# EEM_connector_Magneto.net
KiCad netlist of a schematic drawn in Altium Designer
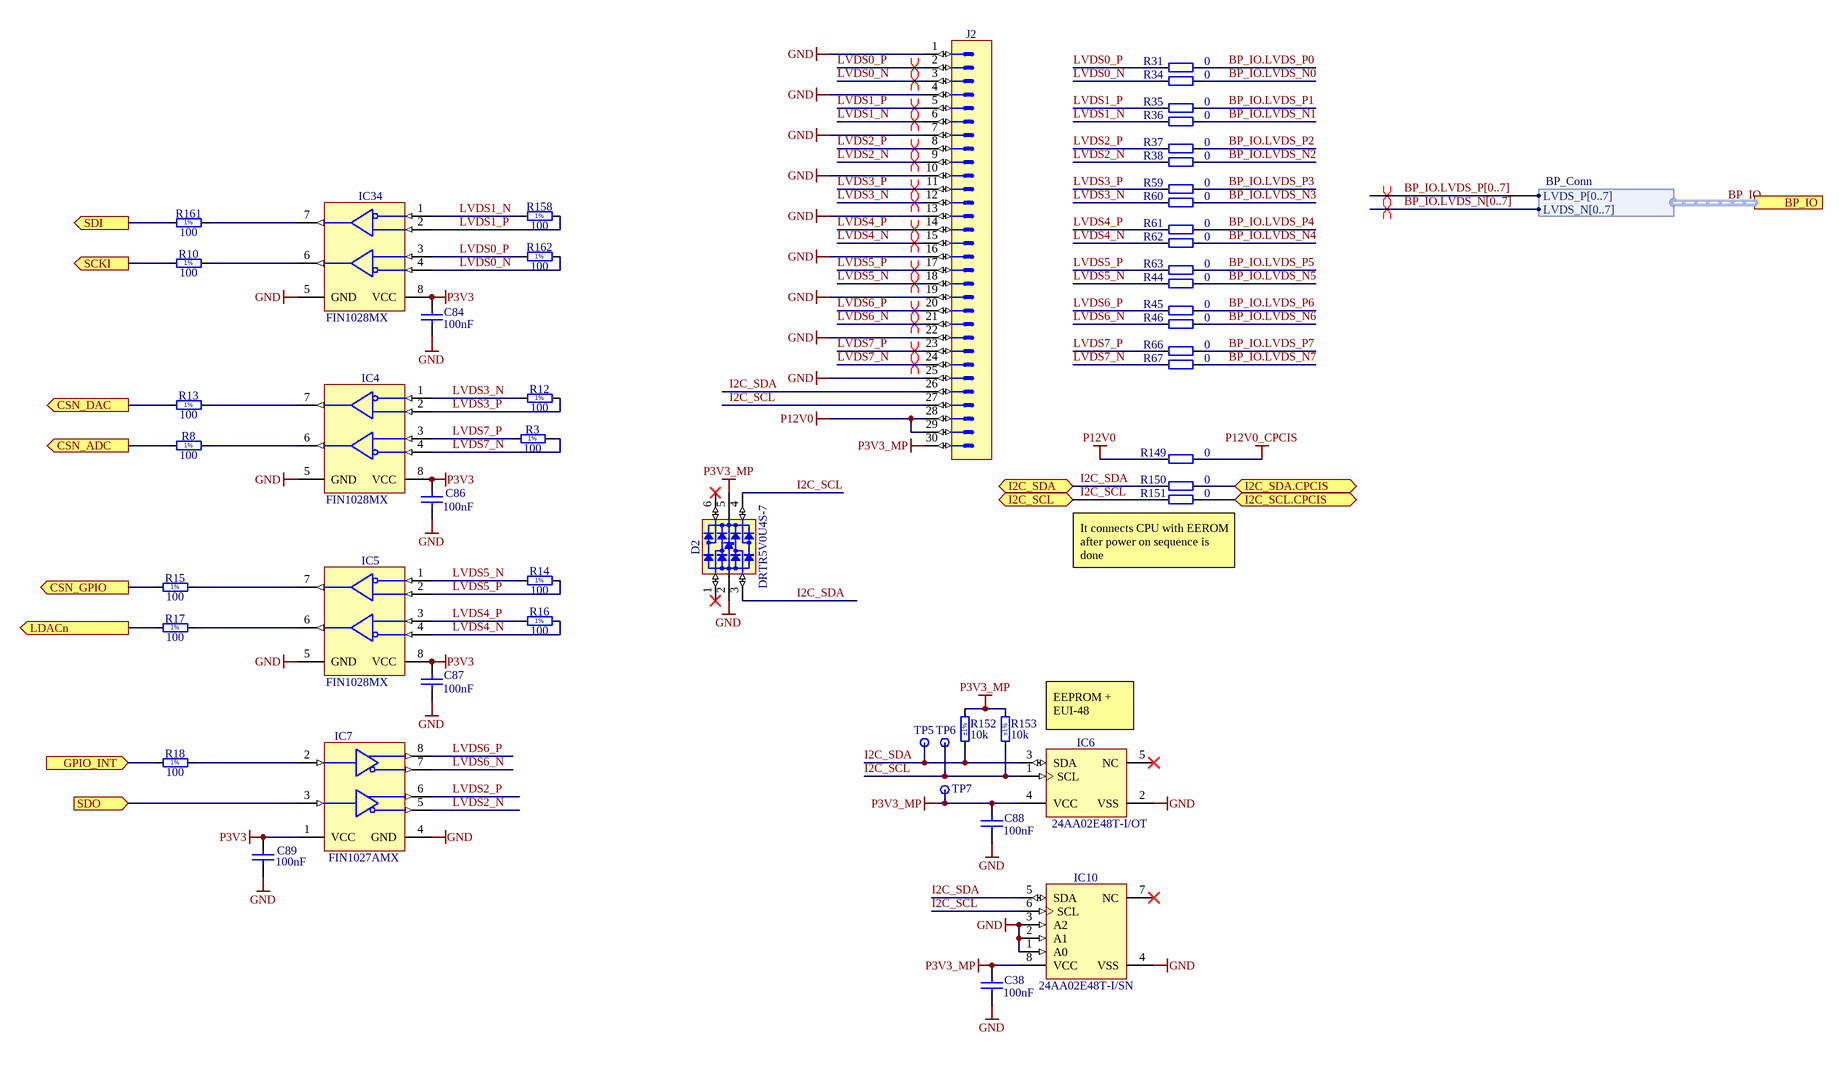
[diagram p0: EEM_connector_Magneto.SchDoc]

(export (version "E")
  (design (tool "Eeschema 10.0.6"))
  (components
    (comp (ref "C38")
      (value "100nF")
      (footprint "CAPC1005X55N")
      (description "Non-polarised capacitor")
      (fields
        (field (name "PART NUMBER") "CC0402_100NF_16V_10%_X5R")
        (field (name "VOLTAGE") "16V")
        (field (name "AUTHOR") "CERN DEM JLC")
      )
      (libsource (lib "Capacitors") (part "Capacitor - non polarized"))
    )
    (comp (ref "C84")
      (value "100nF")
      (footprint "CAPC1005X55N")
      (description "Non-polarised capacitor")
      (fields
        (field (name "PART NUMBER") "CC0402_100NF_16V_10%_X5R")
        (field (name "VOLTAGE") "16V")
        (field (name "AUTHOR") "CERN DEM JLC")
      )
      (libsource (lib "Capacitors") (part "Capacitor - non polarized"))
    )
    (comp (ref "C86")
      (value "100nF")
      (footprint "CAPC1005X55N")
      (description "Non-polarised capacitor")
      (fields
        (field (name "PART NUMBER") "CC0402_100NF_16V_10%_X5R")
        (field (name "VOLTAGE") "16V")
        (field (name "AUTHOR") "CERN DEM JLC")
      )
      (libsource (lib "Capacitors") (part "Capacitor - non polarized"))
    )
    (comp (ref "C87")
      (value "100nF")
      (footprint "CAPC1005X55N")
      (description "Non-polarised capacitor")
      (fields
        (field (name "PART NUMBER") "CC0402_100NF_16V_10%_X5R")
        (field (name "VOLTAGE") "16V")
        (field (name "AUTHOR") "CERN DEM JLC")
      )
      (libsource (lib "Capacitors") (part "Capacitor - non polarized"))
    )
    (comp (ref "C88")
      (value "100nF")
      (footprint "CAPC1005X55N")
      (description "Non-polarised capacitor")
      (fields
        (field (name "PART NUMBER") "CC0402_100NF_16V_10%_X5R")
        (field (name "VOLTAGE") "16V")
        (field (name "AUTHOR") "CERN DEM JLC")
      )
      (libsource (lib "Capacitors") (part "Capacitor - non polarized"))
    )
    (comp (ref "C89")
      (value "100nF")
      (footprint "CAPC1005X55N")
      (description "Non-polarised capacitor")
      (fields
        (field (name "PART NUMBER") "CC0402_100NF_16V_10%_X5R")
        (field (name "VOLTAGE") "16V")
        (field (name "AUTHOR") "CERN DEM JLC")
      )
      (libsource (lib "Capacitors") (part "Capacitor - non polarized"))
    )
    (comp (ref "D2")
      (value "DRTR5V0U4S-7")
      (footprint "SOT65P210X110-6N")
      (description "Integrated Quad Ultra-Low Capacitance ESD Protection")
      (fields (field (name "AUTHOR") "GK"))
      (libsource (lib "Diodes") (part "D_TVS_DRTR5V0U4S-7"))
    )
    (comp (ref "IC4")
      (value "FIN1028MX")
      (footprint "SOIC127P600X175-8N")
      (description "3.3V LVDS 2-Bit High-Speed Differential Reciever")
      (fields (field (name "AUTHOR") "GK"))
      (libsource (lib "LIBRARY_SCH") (part "IFC_FIN1028"))
    )
    (comp (ref "IC5")
      (value "FIN1028MX")
      (footprint "SOIC127P600X175-8N")
      (description "3.3V LVDS 2-Bit High-Speed Differential Reciever")
      (fields (field (name "AUTHOR") "GK"))
      (libsource (lib "LIBRARY_SCH") (part "IFC_FIN1028"))
    )
    (comp (ref "IC6")
      (value "24AA02E48T-I/OT")
      (footprint "SOT95P280X145-5N")
      (description "1.7V-5.5V, 2K I2C Serial EEPROM With EUI-48 Node Identity")
      (fields (field (name "MANUFACTURER") "MICROCHIP TECHNOLOGY") (field (name "AUTHOR") "CERN DEM MR"))
      (libsource (lib "ICs And Semiconductors") (part "24AA02E48T-I/OT"))
    )
    (comp (ref "IC7")
      (value "FIN1027AMX")
      (footprint "SOIC127P600X175-8N")
      (description "3.3V LVDS, 2-Bit, High-Speed, Differential Driver")
      (fields (field (name "AUTHOR") "GK"))
      (libsource (lib "LIBRARY_SCH") (part "IFC_FIN1027A"))
    )
    (comp (ref "IC10")
      (value "24AA02E48T-I/SN")
      (footprint "SOIC127P600X175-8N")
      (description "1.7V-5.5V, 2K I2C™ Serial EEPROMs with EUI-48™ Node Identity")
      (fields (field (name "AUTHOR") "CERN DEM MR"))
      (libsource (lib "ICs And Semiconductors") (part "24AA025E48-I/SN"))
    )
    (comp (ref "IC34")
      (value "FIN1028MX")
      (footprint "SOIC127P600X175-8N")
      (description "3.3V LVDS 2-Bit High-Speed Differential Reciever")
      (fields (field (name "AUTHOR") "GK"))
      (libsource (lib "LIBRARY_SCH") (part "IFC_FIN1028"))
    )
    (comp (ref "J2")
      (value "IDC")
      (footprint "3M_N2530-6002RB")
      (description "Connector 30 Male")
      (fields
        (field (name "PART NUMBER") "3M_N2530-6002RB")
        (field (name "MANUFACTURER") "3M")
        (field (name "AUTHOR") "CERN DEM JLC")
      )
      (libsource (lib "Connectors") (part "Connector 30 Male"))
    )
    (comp (ref "R3")
      (value "100")
      (footprint "RESC1005X40N")
      (description "Resistor - 1%")
      (fields
        (field (name "PART NUMBER") "R0402_100R_1%_0.0625W_100PPM")
        (field (name "POWER") "0.0625W")
        (field (name "AUTHOR") "CERN DEM JLC")
      )
      (libsource (lib "Resistors") (part "Resistor - 1%"))
    )
    (comp (ref "R8")
      (value "100")
      (footprint "RESC1005X40N")
      (description "Resistor - 1%")
      (fields
        (field (name "PART NUMBER") "R0402_100R_1%_0.0625W_100PPM")
        (field (name "POWER") "0.0625W")
        (field (name "AUTHOR") "CERN DEM JLC")
      )
      (libsource (lib "Resistors") (part "Resistor - 1%"))
    )
    (comp (ref "R10")
      (value "100")
      (footprint "RESC1005X40N")
      (description "Resistor - 1%")
      (fields
        (field (name "PART NUMBER") "R0402_100R_1%_0.0625W_100PPM")
        (field (name "POWER") "0.0625W")
        (field (name "AUTHOR") "CERN DEM JLC")
      )
      (libsource (lib "Resistors") (part "Resistor - 1%"))
    )
    (comp (ref "R12")
      (value "100")
      (footprint "RESC1005X40N")
      (description "Resistor - 1%")
      (fields
        (field (name "PART NUMBER") "R0402_100R_1%_0.0625W_100PPM")
        (field (name "POWER") "0.0625W")
        (field (name "AUTHOR") "CERN DEM JLC")
      )
      (libsource (lib "Resistors") (part "Resistor - 1%"))
    )
    (comp (ref "R13")
      (value "100")
      (footprint "RESC1005X40N")
      (description "Resistor - 1%")
      (fields
        (field (name "PART NUMBER") "R0402_100R_1%_0.0625W_100PPM")
        (field (name "POWER") "0.0625W")
        (field (name "AUTHOR") "CERN DEM JLC")
      )
      (libsource (lib "Resistors") (part "Resistor - 1%"))
    )
    (comp (ref "R14")
      (value "100")
      (footprint "RESC1005X40N")
      (description "Resistor - 1%")
      (fields
        (field (name "PART NUMBER") "R0402_100R_1%_0.0625W_100PPM")
        (field (name "POWER") "0.0625W")
        (field (name "AUTHOR") "CERN DEM JLC")
      )
      (libsource (lib "Resistors") (part "Resistor - 1%"))
    )
    (comp (ref "R15")
      (value "100")
      (footprint "RESC1005X40N")
      (description "Resistor - 1%")
      (fields
        (field (name "PART NUMBER") "R0402_100R_1%_0.0625W_100PPM")
        (field (name "POWER") "0.0625W")
        (field (name "AUTHOR") "CERN DEM JLC")
      )
      (libsource (lib "Resistors") (part "Resistor - 1%"))
    )
    (comp (ref "R16")
      (value "100")
      (footprint "RESC1005X40N")
      (description "Resistor - 1%")
      (fields
        (field (name "PART NUMBER") "R0402_100R_1%_0.0625W_100PPM")
        (field (name "POWER") "0.0625W")
        (field (name "AUTHOR") "CERN DEM JLC")
      )
      (libsource (lib "Resistors") (part "Resistor - 1%"))
    )
    (comp (ref "R17")
      (value "100")
      (footprint "RESC1005X40N")
      (description "Resistor - 1%")
      (fields
        (field (name "PART NUMBER") "R0402_100R_1%_0.0625W_100PPM")
        (field (name "POWER") "0.0625W")
        (field (name "AUTHOR") "CERN DEM JLC")
      )
      (libsource (lib "Resistors") (part "Resistor - 1%"))
    )
    (comp (ref "R18")
      (value "100")
      (footprint "RESC1005X40N")
      (description "Resistor - 1%")
      (fields
        (field (name "PART NUMBER") "R0402_100R_1%_0.0625W_100PPM")
        (field (name "POWER") "0.0625W")
        (field (name "AUTHOR") "CERN DEM JLC")
      )
      (libsource (lib "Resistors") (part "Resistor - 1%"))
    )
    (comp (ref "R31")
      (value "0")
      (footprint "RESC1005X40N")
      (description "Resistor")
      (fields
        (field (name "PART NUMBER") "R0402_0R_JUMPER")
        (field (name "MANUFACTURER") "GENERIC")
        (field (name "AUTHOR") "CERN DEM JLC")
      )
      (libsource (lib "Resistors") (part "Resistor"))
    )
    (comp (ref "R34")
      (value "0")
      (footprint "RESC1005X40N")
      (description "Resistor")
      (fields
        (field (name "PART NUMBER") "R0402_0R_JUMPER")
        (field (name "MANUFACTURER") "GENERIC")
        (field (name "AUTHOR") "CERN DEM JLC")
      )
      (libsource (lib "Resistors") (part "Resistor"))
    )
    (comp (ref "R35")
      (value "0")
      (footprint "RESC1005X40N")
      (description "Resistor")
      (fields
        (field (name "PART NUMBER") "R0402_0R_JUMPER")
        (field (name "MANUFACTURER") "GENERIC")
        (field (name "AUTHOR") "CERN DEM JLC")
      )
      (libsource (lib "Resistors") (part "Resistor"))
    )
    (comp (ref "R36")
      (value "0")
      (footprint "RESC1005X40N")
      (description "Resistor")
      (fields
        (field (name "PART NUMBER") "R0402_0R_JUMPER")
        (field (name "MANUFACTURER") "GENERIC")
        (field (name "AUTHOR") "CERN DEM JLC")
      )
      (libsource (lib "Resistors") (part "Resistor"))
    )
    (comp (ref "R37")
      (value "0")
      (footprint "RESC1005X40N")
      (description "Resistor")
      (fields
        (field (name "PART NUMBER") "R0402_0R_JUMPER")
        (field (name "MANUFACTURER") "GENERIC")
        (field (name "AUTHOR") "CERN DEM JLC")
      )
      (libsource (lib "Resistors") (part "Resistor"))
    )
    (comp (ref "R38")
      (value "0")
      (footprint "RESC1005X40N")
      (description "Resistor")
      (fields
        (field (name "PART NUMBER") "R0402_0R_JUMPER")
        (field (name "MANUFACTURER") "GENERIC")
        (field (name "AUTHOR") "CERN DEM JLC")
      )
      (libsource (lib "Resistors") (part "Resistor"))
    )
    (comp (ref "R44")
      (value "0")
      (footprint "RESC1005X40N")
      (description "Resistor")
      (fields
        (field (name "PART NUMBER") "R0402_0R_JUMPER")
        (field (name "MANUFACTURER") "GENERIC")
        (field (name "AUTHOR") "CERN DEM JLC")
      )
      (libsource (lib "Resistors") (part "Resistor"))
    )
    (comp (ref "R45")
      (value "0")
      (footprint "RESC1005X40N")
      (description "Resistor")
      (fields
        (field (name "PART NUMBER") "R0402_0R_JUMPER")
        (field (name "MANUFACTURER") "GENERIC")
        (field (name "AUTHOR") "CERN DEM JLC")
      )
      (libsource (lib "Resistors") (part "Resistor"))
    )
    (comp (ref "R46")
      (value "0")
      (footprint "RESC1005X40N")
      (description "Resistor")
      (fields
        (field (name "PART NUMBER") "R0402_0R_JUMPER")
        (field (name "MANUFACTURER") "GENERIC")
        (field (name "AUTHOR") "CERN DEM JLC")
      )
      (libsource (lib "Resistors") (part "Resistor"))
    )
    (comp (ref "R59")
      (value "0")
      (footprint "RESC1005X40N")
      (description "Resistor")
      (fields
        (field (name "PART NUMBER") "R0402_0R_JUMPER")
        (field (name "MANUFACTURER") "GENERIC")
        (field (name "AUTHOR") "CERN DEM JLC")
      )
      (libsource (lib "Resistors") (part "Resistor"))
    )
    (comp (ref "R60")
      (value "0")
      (footprint "RESC1005X40N")
      (description "Resistor")
      (fields
        (field (name "PART NUMBER") "R0402_0R_JUMPER")
        (field (name "MANUFACTURER") "GENERIC")
        (field (name "AUTHOR") "CERN DEM JLC")
      )
      (libsource (lib "Resistors") (part "Resistor"))
    )
    (comp (ref "R61")
      (value "0")
      (footprint "RESC1005X40N")
      (description "Resistor")
      (fields
        (field (name "PART NUMBER") "R0402_0R_JUMPER")
        (field (name "MANUFACTURER") "GENERIC")
        (field (name "AUTHOR") "CERN DEM JLC")
      )
      (libsource (lib "Resistors") (part "Resistor"))
    )
    (comp (ref "R62")
      (value "0")
      (footprint "RESC1005X40N")
      (description "Resistor")
      (fields
        (field (name "PART NUMBER") "R0402_0R_JUMPER")
        (field (name "MANUFACTURER") "GENERIC")
        (field (name "AUTHOR") "CERN DEM JLC")
      )
      (libsource (lib "Resistors") (part "Resistor"))
    )
    (comp (ref "R63")
      (value "0")
      (footprint "RESC1005X40N")
      (description "Resistor")
      (fields
        (field (name "PART NUMBER") "R0402_0R_JUMPER")
        (field (name "MANUFACTURER") "GENERIC")
        (field (name "AUTHOR") "CERN DEM JLC")
      )
      (libsource (lib "Resistors") (part "Resistor"))
    )
    (comp (ref "R66")
      (value "0")
      (footprint "RESC1005X40N")
      (description "Resistor")
      (fields
        (field (name "PART NUMBER") "R0402_0R_JUMPER")
        (field (name "MANUFACTURER") "GENERIC")
        (field (name "AUTHOR") "CERN DEM JLC")
      )
      (libsource (lib "Resistors") (part "Resistor"))
    )
    (comp (ref "R67")
      (value "0")
      (footprint "RESC1005X40N")
      (description "Resistor")
      (fields
        (field (name "PART NUMBER") "R0402_0R_JUMPER")
        (field (name "MANUFACTURER") "GENERIC")
        (field (name "AUTHOR") "CERN DEM JLC")
      )
      (libsource (lib "Resistors") (part "Resistor"))
    )
    (comp (ref "R149")
      (value "0")
      (footprint "RESC2012X60N")
      (description "Resistor")
      (fields
        (field (name "PART NUMBER") "R0805_0R_JUMPER")
        (field (name "MANUFACTURER") "GENERIC")
        (field (name "AUTHOR") "CERN DEM JLC")
      )
      (libsource (lib "Resistors") (part "Resistor"))
    )
    (comp (ref "R150")
      (value "0")
      (footprint "RESC1005X40N")
      (description "Resistor")
      (fields
        (field (name "PART NUMBER") "R0402_0R_JUMPER")
        (field (name "MANUFACTURER") "GENERIC")
        (field (name "AUTHOR") "CERN DEM JLC")
      )
      (libsource (lib "Resistors") (part "Resistor"))
    )
    (comp (ref "R151")
      (value "0")
      (footprint "RESC1005X40N")
      (description "Resistor")
      (fields
        (field (name "PART NUMBER") "R0402_0R_JUMPER")
        (field (name "MANUFACTURER") "GENERIC")
        (field (name "AUTHOR") "CERN DEM JLC")
      )
      (libsource (lib "Resistors") (part "Resistor"))
    )
    (comp (ref "R152")
      (value "10k")
      (footprint "RESC1005X40N")
      (description "Resistor - 1%")
      (fields
        (field (name "TOLERANCE") "±1%")
        (field (name "PART NUMBER") "R0402_10K_1%_0.0625W_100PPM")
        (field (name "POWER") "0.0625W")
        (field (name "AUTHOR") "CERN DEM JLC")
      )
      (libsource (lib "Resistors") (part "Resistor - 1%"))
    )
    (comp (ref "R153")
      (value "10k")
      (footprint "RESC1005X40N")
      (description "Resistor - 1%")
      (fields
        (field (name "TOLERANCE") "±1%")
        (field (name "PART NUMBER") "R0402_10K_1%_0.0625W_100PPM")
        (field (name "POWER") "0.0625W")
        (field (name "AUTHOR") "CERN DEM JLC")
      )
      (libsource (lib "Resistors") (part "Resistor - 1%"))
    )
    (comp (ref "R158")
      (value "100")
      (footprint "RESC1005X40N")
      (description "Resistor - 1%")
      (fields
        (field (name "PART NUMBER") "R0402_100R_1%_0.0625W_100PPM")
        (field (name "POWER") "0.0625W")
        (field (name "AUTHOR") "CERN DEM JLC")
      )
      (libsource (lib "Resistors") (part "Resistor - 1%"))
    )
    (comp (ref "R161")
      (value "100")
      (footprint "RESC1005X40N")
      (description "Resistor - 1%")
      (fields
        (field (name "PART NUMBER") "R0402_100R_1%_0.0625W_100PPM")
        (field (name "POWER") "0.0625W")
        (field (name "AUTHOR") "CERN DEM JLC")
      )
      (libsource (lib "Resistors") (part "Resistor - 1%"))
    )
    (comp (ref "R162")
      (value "100")
      (footprint "RESC1005X40N")
      (description "Resistor - 1%")
      (fields
        (field (name "PART NUMBER") "R0402_100R_1%_0.0625W_100PPM")
        (field (name "POWER") "0.0625W")
        (field (name "AUTHOR") "CERN DEM JLC")
      )
      (libsource (lib "Resistors") (part "Resistor - 1%"))
    )
    (comp (ref "TP5")
      (value "Test Point")
      (footprint "TPS127")
      (fields (field (name "PART NUMBER") "SMD_PAD_1.27X1.27MM") (field (name "AUTHOR") "CERN DEM JLC"))
      (libsource (lib "Eletro-mechanical") (part "Test Point"))
    )
    (comp (ref "TP6")
      (value "Test Point")
      (footprint "TPS127")
      (fields (field (name "PART NUMBER") "SMD_PAD_1.27X1.27MM") (field (name "AUTHOR") "CERN DEM JLC"))
      (libsource (lib "Eletro-mechanical") (part "Test Point"))
    )
    (comp (ref "TP7")
      (value "Test Point")
      (footprint "TPS127")
      (fields (field (name "PART NUMBER") "SMD_PAD_1.27X1.27MM") (field (name "AUTHOR") "CERN DEM JLC"))
      (libsource (lib "Eletro-mechanical") (part "Test Point"))
    )
  )
  (nets
    (net (code "2") (name "/BP_IO.LVDS_N0") (class "Default")
      (node (ref "R34") (pin "2") (pinfunction "2_2") (pintype "passive"))
    )
    (net (code "3") (name "/BP_IO.LVDS_N1") (class "Default")
      (node (ref "R36") (pin "2") (pinfunction "2_2") (pintype "passive"))
    )
    (net (code "4") (name "/BP_IO.LVDS_N2") (class "Default")
      (node (ref "R38") (pin "2") (pinfunction "2_2") (pintype "passive"))
    )
    (net (code "5") (name "/BP_IO.LVDS_N3") (class "Default")
      (node (ref "R60") (pin "2") (pinfunction "2_2") (pintype "passive"))
    )
    (net (code "6") (name "/BP_IO.LVDS_N4") (class "Default")
      (node (ref "R62") (pin "2") (pinfunction "2_2") (pintype "passive"))
    )
    (net (code "7") (name "/BP_IO.LVDS_N5") (class "Default")
      (node (ref "R44") (pin "2") (pinfunction "2_2") (pintype "passive"))
    )
    (net (code "8") (name "/BP_IO.LVDS_N6") (class "Default")
      (node (ref "R46") (pin "2") (pinfunction "2_2") (pintype "passive"))
    )
    (net (code "9") (name "/BP_IO.LVDS_N7") (class "Default")
      (node (ref "R67") (pin "2") (pinfunction "2_2") (pintype "passive"))
    )
    (net (code "11") (name "/BP_IO.LVDS_P0") (class "Default")
      (node (ref "R31") (pin "2") (pinfunction "2_2") (pintype "passive"))
    )
    (net (code "12") (name "/BP_IO.LVDS_P1") (class "Default")
      (node (ref "R35") (pin "2") (pinfunction "2_2") (pintype "passive"))
    )
    (net (code "13") (name "/BP_IO.LVDS_P2") (class "Default")
      (node (ref "R37") (pin "2") (pinfunction "2_2") (pintype "passive"))
    )
    (net (code "14") (name "/BP_IO.LVDS_P3") (class "Default")
      (node (ref "R59") (pin "2") (pinfunction "2_2") (pintype "passive"))
    )
    (net (code "15") (name "/BP_IO.LVDS_P4") (class "Default")
      (node (ref "R61") (pin "2") (pinfunction "2_2") (pintype "passive"))
    )
    (net (code "16") (name "/BP_IO.LVDS_P5") (class "Default")
      (node (ref "R63") (pin "2") (pinfunction "2_2") (pintype "passive"))
    )
    (net (code "17") (name "/BP_IO.LVDS_P6") (class "Default")
      (node (ref "R45") (pin "2") (pinfunction "2_2") (pintype "passive"))
    )
    (net (code "18") (name "/BP_IO.LVDS_P7") (class "Default")
      (node (ref "R66") (pin "2") (pinfunction "2_2") (pintype "passive"))
    )
    (net (code "21") (name "/CSN_ADC") (class "Default")
      (node (ref "R8") (pin "1") (pinfunction "1_1") (pintype "passive"))
    )
    (net (code "22") (name "/CSN_DAC") (class "Default")
      (node (ref "R13") (pin "1") (pinfunction "1_1") (pintype "passive"))
    )
    (net (code "23") (name "/CSN_GPIO") (class "Default")
      (node (ref "R15") (pin "1") (pinfunction "1_1") (pintype "passive"))
    )
    (net (code "24") (name "/GPIO_INT") (class "Default")
      (node (ref "R18") (pin "1") (pinfunction "1_1") (pintype "passive"))
    )
    (net (code "25") (name "/I2C_SCL") (class "Default")
      (node (ref "D2") (pin "4") (pinfunction "I/O3_4") (pintype "bidirectional"))
      (node (ref "IC10") (pin "6") (pinfunction "SCL_6") (pintype "input"))
      (node (ref "IC6") (pin "1") (pinfunction "SCL_1") (pintype "input"))
      (node (ref "J2") (pin "27") (pinfunction "27_27") (pintype "bidirectional"))
      (node (ref "R151") (pin "1") (pinfunction "1_1") (pintype "passive"))
      (node (ref "R153") (pin "1") (pinfunction "1_1") (pintype "passive"))
      (node (ref "TP6") (pin "1") (pinfunction "1_1") (pintype "bidirectional"))
    )
    (net (code "26") (name "/I2C_SCL.CPCIS") (class "Default")
      (node (ref "R151") (pin "2") (pinfunction "2_2") (pintype "passive"))
    )
    (net (code "27") (name "/I2C_SDA") (class "Default")
      (node (ref "D2") (pin "3") (pinfunction "I/O2_3") (pintype "bidirectional"))
      (node (ref "IC10") (pin "5") (pinfunction "SDA_5") (pintype "bidirectional"))
      (node (ref "IC6") (pin "3") (pinfunction "SDA_3") (pintype "bidirectional"))
      (node (ref "J2") (pin "26") (pinfunction "26_26") (pintype "bidirectional"))
      (node (ref "R150") (pin "1") (pinfunction "1_1") (pintype "passive"))
      (node (ref "R152") (pin "1") (pinfunction "1_1") (pintype "passive"))
      (node (ref "TP5") (pin "1") (pinfunction "1_1") (pintype "bidirectional"))
    )
    (net (code "28") (name "/I2C_SDA.CPCIS") (class "Default")
      (node (ref "R150") (pin "2") (pinfunction "2_2") (pintype "passive"))
    )
    (net (code "29") (name "/LDACn") (class "Default")
      (node (ref "R17") (pin "1") (pinfunction "1_1") (pintype "passive"))
    )
    (net (code "30") (name "/LVDS0_N") (class "Default")
      (node (ref "IC34") (pin "4") (pinfunction "RIN2-_4") (pintype "input"))
      (node (ref "J2") (pin "3") (pinfunction "3_3") (pintype "bidirectional"))
      (node (ref "R162") (pin "2") (pinfunction "2_2") (pintype "passive"))
      (node (ref "R34") (pin "1") (pinfunction "1_1") (pintype "passive"))
    )
    (net (code "31") (name "/LVDS0_P") (class "Default")
      (node (ref "IC34") (pin "3") (pinfunction "RIN2+_3") (pintype "input"))
      (node (ref "J2") (pin "2") (pinfunction "2_2") (pintype "bidirectional"))
      (node (ref "R162") (pin "1") (pinfunction "1_1") (pintype "passive"))
      (node (ref "R31") (pin "1") (pinfunction "1_1") (pintype "passive"))
    )
    (net (code "32") (name "/LVDS1_N") (class "Default")
      (node (ref "IC34") (pin "1") (pinfunction "RIN1-_1") (pintype "input"))
      (node (ref "J2") (pin "6") (pinfunction "6_6") (pintype "bidirectional"))
      (node (ref "R158") (pin "1") (pinfunction "1_1") (pintype "passive"))
      (node (ref "R36") (pin "1") (pinfunction "1_1") (pintype "passive"))
    )
    (net (code "33") (name "/LVDS1_P") (class "Default")
      (node (ref "IC34") (pin "2") (pinfunction "RIN1+_2") (pintype "input"))
      (node (ref "J2") (pin "5") (pinfunction "5_5") (pintype "bidirectional"))
      (node (ref "R158") (pin "2") (pinfunction "2_2") (pintype "passive"))
      (node (ref "R35") (pin "1") (pinfunction "1_1") (pintype "passive"))
    )
    (net (code "34") (name "/LVDS2_N") (class "Default")
      (node (ref "IC7") (pin "5") (pinfunction "DOUT-_5") (pintype "output"))
      (node (ref "J2") (pin "9") (pinfunction "9_9") (pintype "bidirectional"))
      (node (ref "R38") (pin "1") (pinfunction "1_1") (pintype "passive"))
    )
    (net (code "35") (name "/LVDS2_P") (class "Default")
      (node (ref "IC7") (pin "6") (pinfunction "DOUT+_6") (pintype "output"))
      (node (ref "J2") (pin "8") (pinfunction "8_8") (pintype "bidirectional"))
      (node (ref "R37") (pin "1") (pinfunction "1_1") (pintype "passive"))
    )
    (net (code "36") (name "/LVDS3_N") (class "Default")
      (node (ref "IC4") (pin "1") (pinfunction "RIN1-_1") (pintype "input"))
      (node (ref "J2") (pin "12") (pinfunction "12_12") (pintype "bidirectional"))
      (node (ref "R12") (pin "1") (pinfunction "1_1") (pintype "passive"))
      (node (ref "R60") (pin "1") (pinfunction "1_1") (pintype "passive"))
    )
    (net (code "37") (name "/LVDS3_P") (class "Default")
      (node (ref "IC4") (pin "2") (pinfunction "RIN1+_2") (pintype "input"))
      (node (ref "J2") (pin "11") (pinfunction "11_11") (pintype "bidirectional"))
      (node (ref "R12") (pin "2") (pinfunction "2_2") (pintype "passive"))
      (node (ref "R59") (pin "1") (pinfunction "1_1") (pintype "passive"))
    )
    (net (code "38") (name "/LVDS4_N") (class "Default")
      (node (ref "IC5") (pin "4") (pinfunction "RIN2-_4") (pintype "input"))
      (node (ref "J2") (pin "15") (pinfunction "15_15") (pintype "bidirectional"))
      (node (ref "R16") (pin "2") (pinfunction "2_2") (pintype "passive"))
      (node (ref "R62") (pin "1") (pinfunction "1_1") (pintype "passive"))
    )
    (net (code "39") (name "/LVDS4_P") (class "Default")
      (node (ref "IC5") (pin "3") (pinfunction "RIN2+_3") (pintype "input"))
      (node (ref "J2") (pin "14") (pinfunction "14_14") (pintype "bidirectional"))
      (node (ref "R16") (pin "1") (pinfunction "1_1") (pintype "passive"))
      (node (ref "R61") (pin "1") (pinfunction "1_1") (pintype "passive"))
    )
    (net (code "40") (name "/LVDS5_N") (class "Default")
      (node (ref "IC5") (pin "1") (pinfunction "RIN1-_1") (pintype "input"))
      (node (ref "J2") (pin "18") (pinfunction "18_18") (pintype "bidirectional"))
      (node (ref "R14") (pin "1") (pinfunction "1_1") (pintype "passive"))
      (node (ref "R44") (pin "1") (pinfunction "1_1") (pintype "passive"))
    )
    (net (code "41") (name "/LVDS5_P") (class "Default")
      (node (ref "IC5") (pin "2") (pinfunction "RIN1+_2") (pintype "input"))
      (node (ref "J2") (pin "17") (pinfunction "17_17") (pintype "bidirectional"))
      (node (ref "R14") (pin "2") (pinfunction "2_2") (pintype "passive"))
      (node (ref "R63") (pin "1") (pinfunction "1_1") (pintype "passive"))
    )
    (net (code "42") (name "/LVDS6_N") (class "Default")
      (node (ref "IC7") (pin "7") (pinfunction "DOUT-_7") (pintype "output"))
      (node (ref "J2") (pin "21") (pinfunction "21_21") (pintype "bidirectional"))
      (node (ref "R46") (pin "1") (pinfunction "1_1") (pintype "passive"))
    )
    (net (code "43") (name "/LVDS6_P") (class "Default")
      (node (ref "IC7") (pin "8") (pinfunction "DOUT+_8") (pintype "output"))
      (node (ref "J2") (pin "20") (pinfunction "20_20") (pintype "bidirectional"))
      (node (ref "R45") (pin "1") (pinfunction "1_1") (pintype "passive"))
    )
    (net (code "44") (name "/LVDS7_N") (class "Default")
      (node (ref "IC4") (pin "4") (pinfunction "RIN2-_4") (pintype "input"))
      (node (ref "J2") (pin "24") (pinfunction "24_24") (pintype "bidirectional"))
      (node (ref "R3") (pin "2") (pinfunction "2_2") (pintype "passive"))
      (node (ref "R67") (pin "1") (pinfunction "1_1") (pintype "passive"))
    )
    (net (code "45") (name "/LVDS7_P") (class "Default")
      (node (ref "IC4") (pin "3") (pinfunction "RIN2+_3") (pintype "input"))
      (node (ref "J2") (pin "23") (pinfunction "23_23") (pintype "bidirectional"))
      (node (ref "R3") (pin "1") (pinfunction "1_1") (pintype "passive"))
      (node (ref "R66") (pin "1") (pinfunction "1_1") (pintype "passive"))
    )
    (net (code "46") (name "/SCKI") (class "Default")
      (node (ref "R10") (pin "1") (pinfunction "1_1") (pintype "passive"))
    )
    (net (code "47") (name "/SDI") (class "Default")
      (node (ref "R161") (pin "1") (pinfunction "1_1") (pintype "passive"))
    )
    (net (code "48") (name "/SDO") (class "Default")
      (node (ref "IC7") (pin "3") (pinfunction "DIN2RIN-_3") (pintype "input"))
    )
    (net (code "49") (name "GND") (class "Default")
      (node (ref "C38") (pin "1") (pinfunction "1_1") (pintype "passive"))
      (node (ref "C84") (pin "1") (pinfunction "1_1") (pintype "passive"))
      (node (ref "C86") (pin "1") (pinfunction "1_1") (pintype "passive"))
      (node (ref "C87") (pin "1") (pinfunction "1_1") (pintype "passive"))
      (node (ref "C88") (pin "1") (pinfunction "1_1") (pintype "passive"))
      (node (ref "C89") (pin "1") (pinfunction "1_1") (pintype "passive"))
      (node (ref "D2") (pin "2") (pinfunction "GND_2") (pintype "power_in"))
      (node (ref "IC10") (pin "1") (pinfunction "A0_1") (pintype "input"))
      (node (ref "IC10") (pin "2") (pinfunction "A1_2") (pintype "input"))
      (node (ref "IC10") (pin "3") (pinfunction "A2_3") (pintype "input"))
      (node (ref "IC10") (pin "4") (pinfunction "VSS_4") (pintype "power_in"))
      (node (ref "IC34") (pin "5") (pinfunction "GND_5") (pintype "power_in"))
      (node (ref "IC4") (pin "5") (pinfunction "GND_5") (pintype "power_in"))
      (node (ref "IC5") (pin "5") (pinfunction "GND_5") (pintype "power_in"))
      (node (ref "IC6") (pin "2") (pinfunction "VSS_2") (pintype "power_in"))
      (node (ref "IC7") (pin "4") (pinfunction "GND_4") (pintype "power_in"))
      (node (ref "J2") (pin "1") (pinfunction "1_1") (pintype "bidirectional"))
      (node (ref "J2") (pin "10") (pinfunction "10_10") (pintype "bidirectional"))
      (node (ref "J2") (pin "13") (pinfunction "13_13") (pintype "bidirectional"))
      (node (ref "J2") (pin "16") (pinfunction "16_16") (pintype "bidirectional"))
      (node (ref "J2") (pin "19") (pinfunction "19_19") (pintype "bidirectional"))
      (node (ref "J2") (pin "22") (pinfunction "22_22") (pintype "bidirectional"))
      (node (ref "J2") (pin "25") (pinfunction "25_25") (pintype "bidirectional"))
      (node (ref "J2") (pin "4") (pinfunction "4_4") (pintype "bidirectional"))
      (node (ref "J2") (pin "7") (pinfunction "7_7") (pintype "bidirectional"))
    )
    (net (code "50") (name "Net-(IC4-ROUT1)") (class "Default")
      (node (ref "IC4") (pin "7") (pinfunction "ROUT1_7") (pintype "output"))
      (node (ref "R13") (pin "2") (pinfunction "2_2") (pintype "passive"))
    )
    (net (code "51") (name "Net-(IC4-ROUT2)") (class "Default")
      (node (ref "IC4") (pin "6") (pinfunction "ROUT2_6") (pintype "output"))
      (node (ref "R8") (pin "2") (pinfunction "2_2") (pintype "passive"))
    )
    (net (code "52") (name "Net-(IC5-ROUT1)") (class "Default")
      (node (ref "IC5") (pin "7") (pinfunction "ROUT1_7") (pintype "output"))
      (node (ref "R15") (pin "2") (pinfunction "2_2") (pintype "passive"))
    )
    (net (code "53") (name "Net-(IC5-ROUT2)") (class "Default")
      (node (ref "IC5") (pin "6") (pinfunction "ROUT2_6") (pintype "output"))
      (node (ref "R17") (pin "2") (pinfunction "2_2") (pintype "passive"))
    )
    (net (code "54") (name "Net-(IC7-DIN1)") (class "Default")
      (node (ref "IC7") (pin "2") (pinfunction "DIN1_2") (pintype "input"))
      (node (ref "R18") (pin "2") (pinfunction "2_2") (pintype "passive"))
    )
    (net (code "55") (name "Net-(IC34-ROUT1)") (class "Default")
      (node (ref "IC34") (pin "7") (pinfunction "ROUT1_7") (pintype "output"))
      (node (ref "R161") (pin "2") (pinfunction "2_2") (pintype "passive"))
    )
    (net (code "56") (name "Net-(IC34-ROUT2)") (class "Default")
      (node (ref "IC34") (pin "6") (pinfunction "ROUT2_6") (pintype "output"))
      (node (ref "R10") (pin "2") (pinfunction "2_2") (pintype "passive"))
    )
    (net (code "57") (name "P3V3") (class "Default")
      (node (ref "C84") (pin "2") (pinfunction "2_2") (pintype "passive"))
      (node (ref "C86") (pin "2") (pinfunction "2_2") (pintype "passive"))
      (node (ref "C87") (pin "2") (pinfunction "2_2") (pintype "passive"))
      (node (ref "C89") (pin "2") (pinfunction "2_2") (pintype "passive"))
      (node (ref "IC34") (pin "8") (pinfunction "VCC_8") (pintype "power_in"))
      (node (ref "IC4") (pin "8") (pinfunction "VCC_8") (pintype "power_in"))
      (node (ref "IC5") (pin "8") (pinfunction "VCC_8") (pintype "power_in"))
      (node (ref "IC7") (pin "1") (pinfunction "VCC_1") (pintype "power_in"))
    )
    (net (code "58") (name "P3V3_MP") (class "Default")
      (node (ref "C38") (pin "2") (pinfunction "2_2") (pintype "passive"))
      (node (ref "C88") (pin "2") (pinfunction "2_2") (pintype "passive"))
      (node (ref "D2") (pin "5") (pinfunction "VBUS_5") (pintype "power_in"))
      (node (ref "IC10") (pin "8") (pinfunction "VCC_8") (pintype "power_in"))
      (node (ref "IC6") (pin "4") (pinfunction "VCC_4") (pintype "power_in"))
      (node (ref "J2") (pin "30") (pinfunction "30_30") (pintype "bidirectional"))
      (node (ref "R152") (pin "2") (pinfunction "2_2") (pintype "passive"))
      (node (ref "R153") (pin "2") (pinfunction "2_2") (pintype "passive"))
      (node (ref "TP7") (pin "1") (pinfunction "1_1") (pintype "bidirectional"))
    )
    (net (code "59") (name "P12V0") (class "Default")
      (node (ref "J2") (pin "28") (pinfunction "28_28") (pintype "bidirectional"))
      (node (ref "J2") (pin "29") (pinfunction "29_29") (pintype "bidirectional"))
      (node (ref "R149") (pin "1") (pinfunction "1_1") (pintype "passive"))
    )
    (net (code "60") (name "P12V0_CPCIS") (class "Default")
      (node (ref "R149") (pin "2") (pinfunction "2_2") (pintype "passive"))
    )
    (net (code "61") (name "unconnected-(D2-I{slash}O1-Pad1)") (class "Default")
      (node (ref "D2") (pin "1") (pinfunction "I/O1_1") (pintype "bidirectional+no_connect"))
    )
    (net (code "62") (name "unconnected-(D2-I{slash}O4-Pad6)") (class "Default")
      (node (ref "D2") (pin "6") (pinfunction "I/O4_6") (pintype "bidirectional+no_connect"))
    )
    (net (code "63") (name "unconnected-(IC6-NC-Pad5)") (class "Default")
      (node (ref "IC6") (pin "5") (pinfunction "NC_5") (pintype "passive+no_connect"))
    )
    (net (code "64") (name "unconnected-(IC10-NC-Pad7)") (class "Default")
      (node (ref "IC10") (pin "7") (pinfunction "NC_7") (pintype "passive+no_connect"))
    )
  )
)
